# 12V_ESB.net
KiCad netlist of a schematic drawn in Altium Designer
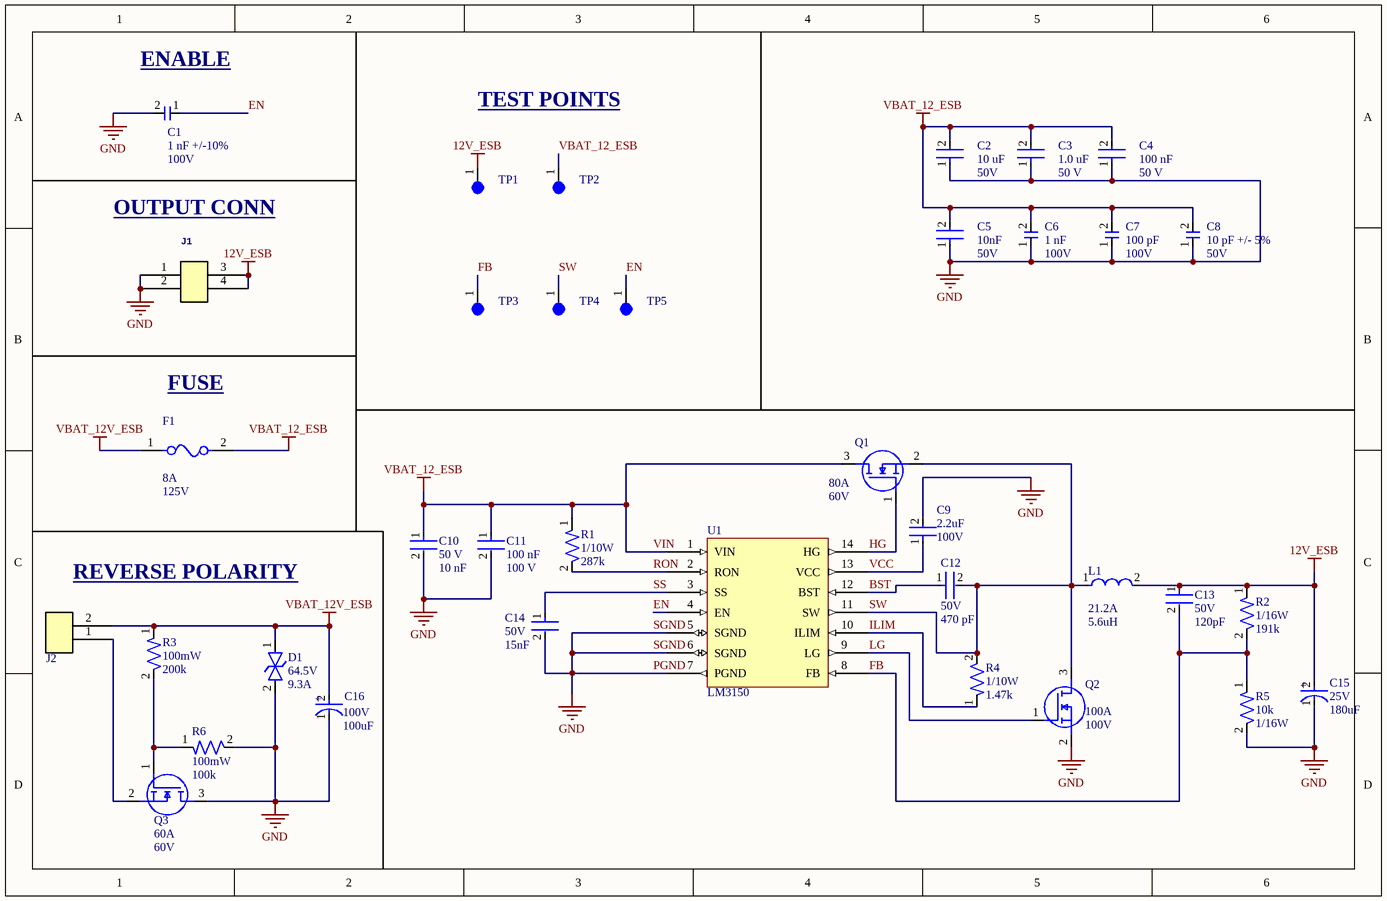
[diagram p0: 12V_ESB.SchDoc]

(export (version "E")
  (design (tool "Eeschema 10.0.6"))
  (components
    (comp (ref "C1")
      (value "C0603Y102K1RAC7867")
      (footprint "CAP-0603")
      (description "1000 pF ±10% 100V Ceramic Capacitor X7R 0603 (1608 Metric)")
      (fields (field (name "CAPACITANCE") "1 nF +/-10%") (field (name "VOLTAGE") "100V"))
      (libsource (lib "MasterLib") (part "CAP-1N-0001"))
    )
    (comp (ref "C2")
      (value "CL32B106KBJNNNE")
      (footprint "JLC_25:CAP-1210")
      (description "CAP CER 10UF 50V X7R 1210")
      (fields (field (name "VOLTAGE") "50V") (field (name "CAPACITANCE") "10 uF"))
      (libsource (lib "JLC_25") (part "CAP-10U-0002"))
    )
    (comp (ref "C3")
      (value "CC0805KKX7R9BB105")
      (footprint "JLC_25:CAP-0805")
      (description "CAP CER 1UF 50V X7R 0805")
      (fields (field (name "VOLTAGE") "50 V") (field (name "CAPACITANCE") "1.0 uF"))
      (libsource (lib "JLC_25") (part "CAP-1U-0001"))
    )
    (comp (ref "C4")
      (value "CC0805KRX7R9BB104")
      (footprint "JLC_25:CAP-0805")
      (description "CAP CER 0.1UF 50V X7R 0805")
      (fields (field (name "VOLTAGE RATING") "50 V") (field (name "CAPACITANCE") "100 nF"))
      (libsource (lib "JLC_25") (part "CAP-0.1U-0002"))
    )
    (comp (ref "C5")
      (value "GRM2195C1H103JA01D")
      (footprint "JLC_25:CAP-0805")
      (description "CAP CER 10000PF 50V C0G/NP0 0805")
      (fields (field (name "VOLTAGE") "50V") (field (name "CAPACITANCE") "10nF"))
      (libsource (lib "JLC_25") (part "CAP-10N-0001"))
    )
    (comp (ref "C6")
      (value "CDR01BX102BKUS7185")
      (footprint "CAP-0805")
      (description "1000 pF ±10% 100V Ceramic Capacitor BX 0805 (2012 Metric)")
      (fields (field (name "CAPACITANCE") "1 nF") (field (name "VOLTAGE RATING") "100V"))
      (libsource (lib "MasterLib") (part "CAP-1N-0003"))
    )
    (comp (ref "C7")
      (value "0603N101J101CT")
      (footprint "CAP-0603")
      (description "100 pF ±5% 100V Ceramic Capacitor C0G, NP0 0603 (1608 Metric)")
      (fields
        (field (name "TOLERANCE") "+/-5%")
        (field (name "CAPACITANCE") "100 pF")
        (field (name "VOLTAGE") "100V")
      )
      (libsource (lib "MasterLib") (part "CAP-100P-0002"))
    )
    (comp (ref "C8")
      (value "0603N100J500CT")
      (footprint "CAP-0603")
      (description "10 pF ±5% 50V Ceramic Capacitor C0G, NP0 0603 (1608 Metric)")
      (fields
        (field (name "MANUFACTURER") "Walshin Technology Corporation")
        (field (name "CAPACITANCE") "10 pF +/- 5%")
        (field (name "VOLTAGE RATING") "50V")
      )
      (libsource (lib "MasterLib") (part "CAP-10P-0001"))
    )
    (comp (ref "C9")
      (value "CC1206KKX7R0BB225")
      (footprint "CAP-1206")
      (description "CAP CER 2.2UF 100V X7R 1206")
      (fields (field (name "CAPACITANCE") "2.2uF") (field (name "VOLTAGE") "100V"))
      (libsource (lib "JLC_25") (part "CAP-2.2U-0001"))
    )
    (comp (ref "C10")
      (value "CC0603KPX7R9BB103")
      (footprint "CAP-0603")
      (description "CAP CER 10000PF 50V X7R 0603")
      (fields (field (name "VOLTAGE") "50 V") (field (name "CAPACITANCE") "10 nF"))
      (libsource (lib "JLC_25") (part "CAP-10N-0002"))
    )
    (comp (ref "C11")
      (value "CC0603KRX7R0BB104")
      (footprint "CAP-0603")
      (description "CAP CER 0.1UF 100V X7R 0603")
      (fields (field (name "CAPACITANCE") "100 nF") (field (name "VOLTAGE") "100 V"))
      (libsource (lib "JLC_25") (part "CAP-100N-0001"))
    )
    (comp (ref "C12")
      (value "CC0805JRNPO9BN471")
      (footprint "CAP-0805")
      (description "CAP CER 470PF 50V C0G/NPO 0805")
      (fields (field (name "VOLTAGE") "50V") (field (name "CAPACITANCE") "470 pF"))
      (libsource (lib "JLC_25") (part "CAP-470P-0001"))
    )
    (comp (ref "C13")
      (value "CC0603JRNPO9BN121")
      (footprint "CAP-0603")
      (description "CAP CER 120PF 50V C0G/NPO 0603")
      (fields (field (name "VOLTAGE") "50V") (field (name "CAPACITANCE") "120pF"))
      (libsource (lib "JLC_25") (part "CAP-120pF-0001"))
    )
    (comp (ref "C14")
      (value "CC0402KRX7R9BB153")
      (footprint "CAP-0402")
      (description "50V 15nF X7R ±10% 0402 Multilayer Ceramic Capacitors MLCC - SMD/SMT ROHS")
      (fields (field (name "VOLTAGE") "50V") (field (name "CAPACITANCE") "15nF"))
      (libsource (lib "JLC_25") (part "CAP-15N-0001"))
    )
    (comp (ref "C15")
      (value "EEE-FNE181XUP")
      (footprint "CAP-180uF")
      (description "CAP ALUM 180UF 20% 25V SMD")
      (fields (field (name "VOLTAGE") "25V") (field (name "CAPACITANCE") "180uF"))
      (libsource (lib "JLC_25") (part "CAP-180uF-0001"))
    )
    (comp (ref "C16")
      (value "100SEV100M12.5X16")
      (footprint "CAP-100U-0002")
      (description "100 µF 100 V Aluminum Electrolytic Capacitors Radial, Can - SMD 2000 Hrs @ 85°C")
      (fields (field (name "VOLTAGE") "100V") (field (name "CAPACITANCE") "100uF"))
      (libsource (lib "JLC_25") (part "CAP-100U-0002"))
    )
    (comp (ref "D1")
      (value "SMBJ40CA")
      (footprint "DO-214AA (SMBJ)")
      (description "TVS DIODE 40VWM 64.5VC DO214AA")
      (fields (field (name "VOLTAGE RATING") "64.5V") (field (name "CURRENT RATING") "9.3A"))
      (libsource (lib "JLC_25") (part "DIO-TVS-0001"))
    )
    (comp (ref "F1")
      (value "01550900M")
      (footprint "FUSE-0001")
      (description "FUSE BLOK CARTRIDGE 125V 10A SMD")
      (fields (field (name "FUSE CURRENT") "8A") (field (name "VOLTAGE RATING") "125V"))
      (libsource (lib "JLC_25") (part "FUSE-0001"))
    )
    (comp (ref "J1")
      (value "Molex 43045-0412")
      (footprint "CONN-4POS-0002")
      (description "CONN HEADER VERT 4POS 3MM")
      (libsource (lib "JLC_25") (part "CONN-4POS-0002"))
    )
    (comp (ref "J2")
      (value "1546927-2")
      (footprint "CONN-1546927-2")
      (libsource (lib "JLC_25") (part "CONN-2POS-0003"))
    )
    (comp (ref "L1")
      (value "FEXL1010A-5R6M")
      (footprint "IND-5.6UH-0002")
      (description "21.2A 5.6uH Integrated molded inductor ±20% 23.6A SMD,11x11.9mm Power Inductors ROHS")
      (fields (field (name "CURRENT RATING") "21.2A") (field (name "INDUCTANCE") "5.6uH"))
      (libsource (lib "JLC_25") (part "IND-5.6U-0002"))
    )
    (comp (ref "Q1")
      (value "RU6080L")
      (footprint "NMOS-80A-0001")
      (description "60V 80A 7mΩ@10V,30A 125W 3V TO-252-2 MOSFETs ROHS")
      (fields (field (name "CONTINUOUS CURRENT") "80A") (field (name "VOLTAGE") "60V"))
      (libsource (lib "JLC_25") (part "NMOS-80A-0001"))
    )
    (comp (ref "Q2")
      (value "CSD19533Q5A")
      (footprint "NMOS-100A")
      (description "100V 100A 7.8mΩ@10V,13A 3.2W 2.8V 1 N-channel VSONP-8(5x6) MOSFETs ROHS")
      (fields (field (name "CONTINUOUS CURRENT") "100A") (field (name "VOLTAGE") "100V"))
      (libsource (lib "JLC_25") (part "NMOS-100A-0001"))
    )
    (comp (ref "Q3")
      (value "CSD18543Q3AT")
      (footprint "IC-8VSONCLIP")
      (description "MOSFET N-CH 60V 12A/60A 8VSON")
      (fields (field (name "VOLTAGE") "60V") (field (name "CONTINUOUS CURRENT") "60A"))
      (libsource (lib "JLC_25") (part "NMOS-60A-0001"))
    )
    (comp (ref "R1")
      (value "RC0603FR-07287KL")
      (footprint "RES-0603")
      (description "RES 287K OHM 1% 1/10W 0603")
      (fields (field (name "POWER") "1/10W") (field (name "RESISTANCE") "287k"))
      (libsource (lib "JLC_25") (part "RES-287k-0001"))
    )
    (comp (ref "R2")
      (value "RC0402FR-07191KL")
      (footprint "RES-0402")
      (description "191 kOhms ±1% 0.063W, 1/16W Chip Resistor 0402 (1005 Metric) Moisture Resistant Thick Film")
      (fields (field (name "POWER") "1/16W") (field (name "RESISTANCE") "191k"))
      (libsource (lib "JLC_25") (part "RES-191k-0001"))
    )
    (comp (ref "R3")
      (value "RC0603FR-07200KL")
      (footprint "RES-0603")
      (description "RES SMD 200K OHM 1% 1/10W 0603")
      (fields
        (field (name "TOLERANCE") "1%")
        (field (name "POWER") "100mW")
        (field (name "RESISTANCE") "200k")
      )
      (libsource (lib "JLC_25") (part "RES-200k-0001"))
    )
    (comp (ref "R4")
      (value "RC0603FR-071K47L")
      (footprint "RES-0603")
      (description "RES 1.47K OHM 1% 1/10W 0603")
      (fields (field (name "POWER") "1/10W") (field (name "RESISTANCE") "1.47k"))
      (libsource (lib "JLC_25") (part "RES-1.47k-0001"))
    )
    (comp (ref "R5")
      (value "RC0402FR-0710KL")
      (footprint "RES-0402")
      (description "RES 10K OHM 1% 1/16W 0402")
      (fields
        (field (name "TOLERANCE") "1%")
        (field (name "RESISTANCE") "10k")
        (field (name "POWER") "1/16W")
      )
      (libsource (lib "JLC_25") (part "RES-10k-0001"))
    )
    (comp (ref "R6")
      (value "RC0603FR-07100KL")
      (footprint "RES-0603")
      (description "RES SMD 100K OHM 1% 1/10W 0603")
      (fields
        (field (name "TOLERANCE") "1%")
        (field (name "POWER") "100mW")
        (field (name "RESISTANCE") "100k")
      )
      (libsource (lib "JLC_25") (part "RES-100k-0001"))
    )
    (comp (ref "TP1")
      (value "5003")
      (footprint "TEST-POINT-0001")
      (description "Oranange PC Test Point, Miniature Phoisphor Bronze Silver Plating Through Hole Mounting Type")
      (libsource (lib "*") (part "TEST-POINT-0001"))
    )
    (comp (ref "TP2")
      (value "5003")
      (footprint "TEST-POINT-0001")
      (description "Oranange PC Test Point, Miniature Phoisphor Bronze Silver Plating Through Hole Mounting Type")
      (libsource (lib "*") (part "TEST-POINT-0001"))
    )
    (comp (ref "TP3")
      (value "5003")
      (footprint "TEST-POINT-0001")
      (description "Oranange PC Test Point, Miniature Phoisphor Bronze Silver Plating Through Hole Mounting Type")
      (libsource (lib "*") (part "TEST-POINT-0001"))
    )
    (comp (ref "TP4")
      (value "5003")
      (footprint "TEST-POINT-0001")
      (description "Oranange PC Test Point, Miniature Phoisphor Bronze Silver Plating Through Hole Mounting Type")
      (libsource (lib "*") (part "TEST-POINT-0001"))
    )
    (comp (ref "TP5")
      (value "5003")
      (footprint "TEST-POINT-0001")
      (description "Oranange PC Test Point, Miniature Phoisphor Bronze Silver Plating Through Hole Mounting Type")
      (libsource (lib "*") (part "TEST-POINT-0001"))
    )
    (comp (ref "U1")
      (value "LM3150")
      (footprint "IC_ESB")
      (description "Buck Regulator Positive Output Step-Down DC-DC Controller IC 14-HTSSOP")
      (libsource (lib "MasterLib") (part "IC-ESB-0001"))
    )
  )
  (nets
    (net (code "1") (name "/BST") (class "Default")
      (node (ref "C12") (pin "1") (pinfunction "1_1") (pintype "passive"))
      (node (ref "U1") (pin "12") (pinfunction "BST_12") (pintype "input"))
    )
    (net (code "2") (name "/EN") (class "Default")
      (node (ref "C1") (pin "1") (pinfunction "1_1") (pintype "passive"))
      (node (ref "TP5") (pin "1") (pinfunction "0_1") (pintype "passive"))
      (node (ref "U1") (pin "4") (pinfunction "EN_4") (pintype "input"))
    )
    (net (code "3") (name "/FB") (class "Default")
      (node (ref "C13") (pin "2") (pinfunction "2_2") (pintype "passive"))
      (node (ref "R2") (pin "2") (pinfunction "2_2") (pintype "passive"))
      (node (ref "R5") (pin "1") (pinfunction "1_1") (pintype "passive"))
      (node (ref "TP3") (pin "1") (pinfunction "0_1") (pintype "passive"))
      (node (ref "U1") (pin "8") (pinfunction "FB_8") (pintype "input"))
    )
    (net (code "4") (name "/HG") (class "Default")
      (node (ref "Q1") (pin "1") (pinfunction "G_1") (pintype "passive"))
      (node (ref "U1") (pin "14") (pinfunction "HG_14") (pintype "output"))
    )
    (net (code "5") (name "/ILIM") (class "Default")
      (node (ref "R4") (pin "1") (pinfunction "1_1") (pintype "passive"))
      (node (ref "U1") (pin "10") (pinfunction "ILIM_10") (pintype "input"))
    )
    (net (code "6") (name "/LG") (class "Default")
      (node (ref "Q2") (pin "1") (pinfunction "G_1") (pintype "passive"))
      (node (ref "U1") (pin "9") (pinfunction "LG_9") (pintype "output"))
    )
    (net (code "7") (name "/RON") (class "Default")
      (node (ref "R1") (pin "2") (pinfunction "2_2") (pintype "passive"))
      (node (ref "U1") (pin "2") (pinfunction "RON_2") (pintype "input"))
    )
    (net (code "8") (name "/SS") (class "Default")
      (node (ref "C14") (pin "1") (pinfunction "1_1") (pintype "passive"))
      (node (ref "U1") (pin "3") (pinfunction "SS_3") (pintype "input"))
    )
    (net (code "9") (name "/SW") (class "Default")
      (node (ref "C12") (pin "2") (pinfunction "2_2") (pintype "passive"))
      (node (ref "L1") (pin "1") (pinfunction "1_1") (pintype "passive"))
      (node (ref "Q1") (pin "2") (pinfunction "S_2") (pintype "passive"))
      (node (ref "Q2") (pin "3") (pinfunction "D_3") (pintype "passive"))
      (node (ref "R4") (pin "2") (pinfunction "2_2") (pintype "passive"))
      (node (ref "TP4") (pin "1") (pinfunction "0_1") (pintype "passive"))
      (node (ref "U1") (pin "11") (pinfunction "SW_11") (pintype "output"))
    )
    (net (code "10") (name "/VCC") (class "Default")
      (node (ref "C9") (pin "1") (pinfunction "1_1") (pintype "passive"))
      (node (ref "U1") (pin "13") (pinfunction "VCC_13") (pintype "output"))
    )
    (net (code "11") (name "12V_ESB") (class "Default")
      (node (ref "C13") (pin "1") (pinfunction "1_1") (pintype "passive"))
      (node (ref "C15") (pin "2") (pinfunction "1_2") (pintype "passive"))
      (node (ref "J1") (pin "3") (pinfunction "3_3") (pintype "passive"))
      (node (ref "J1") (pin "4") (pinfunction "4_4") (pintype "passive"))
      (node (ref "L1") (pin "2") (pinfunction "2_2") (pintype "passive"))
      (node (ref "R2") (pin "1") (pinfunction "1_1") (pintype "passive"))
      (node (ref "TP1") (pin "1") (pinfunction "0_1") (pintype "passive"))
    )
    (net (code "12") (name "GND") (class "Default")
      (node (ref "C1") (pin "2") (pinfunction "2_2") (pintype "passive"))
      (node (ref "C10") (pin "2") (pinfunction "2_2") (pintype "passive"))
      (node (ref "C11") (pin "2") (pinfunction "2_2") (pintype "passive"))
      (node (ref "C14") (pin "2") (pinfunction "2_2") (pintype "passive"))
      (node (ref "C15") (pin "1") (pinfunction "2_1") (pintype "passive"))
      (node (ref "C16") (pin "1") (pinfunction "2_1") (pintype "passive"))
      (node (ref "C2") (pin "1") (pinfunction "1_1") (pintype "passive"))
      (node (ref "C3") (pin "1") (pinfunction "1_1") (pintype "passive"))
      (node (ref "C4") (pin "1") (pinfunction "1_1") (pintype "passive"))
      (node (ref "C5") (pin "1") (pinfunction "1_1") (pintype "passive"))
      (node (ref "C6") (pin "1") (pinfunction "1_1") (pintype "passive"))
      (node (ref "C7") (pin "1") (pinfunction "1_1") (pintype "passive"))
      (node (ref "C8") (pin "1") (pinfunction "1_1") (pintype "passive"))
      (node (ref "C9") (pin "2") (pinfunction "2_2") (pintype "passive"))
      (node (ref "D1") (pin "2") (pintype "passive"))
      (node (ref "J1") (pin "1") (pinfunction "1_1") (pintype "passive"))
      (node (ref "J1") (pin "2") (pinfunction "2_2") (pintype "passive"))
      (node (ref "Q2") (pin "2") (pinfunction "S_2") (pintype "passive"))
      (node (ref "Q3") (pin "3") (pinfunction "D_3") (pintype "passive"))
      (node (ref "R5") (pin "2") (pinfunction "2_2") (pintype "passive"))
      (node (ref "R6") (pin "2") (pinfunction "2_2") (pintype "passive"))
      (node (ref "U1") (pin "5") (pinfunction "SGND_5") (pintype "bidirectional"))
      (node (ref "U1") (pin "6") (pinfunction "SGND_6") (pintype "bidirectional"))
      (node (ref "U1") (pin "7") (pinfunction "PGND_7") (pintype "output"))
    )
    (net (code "13") (name "Net-(J2-7)") (class "Default")
      (node (ref "J2") (pin "1") (pinfunction "7_1") (pintype "passive"))
      (node (ref "Q3") (pin "2") (pinfunction "S_2") (pintype "passive"))
    )
    (net (code "14") (name "Net-(Q3-G)") (class "Default")
      (node (ref "Q3") (pin "1") (pinfunction "G_1") (pintype "passive"))
      (node (ref "R3") (pin "2") (pinfunction "2_2") (pintype "passive"))
      (node (ref "R6") (pin "1") (pinfunction "1_1") (pintype "passive"))
    )
    (net (code "15") (name "VBAT_12V_ESB") (class "Default")
      (node (ref "C16") (pin "2") (pinfunction "1_2") (pintype "passive"))
      (node (ref "D1") (pin "1") (pintype "passive"))
      (node (ref "F1") (pin "1") (pinfunction "1_1") (pintype "passive"))
      (node (ref "J2") (pin "2") (pinfunction "8_2") (pintype "passive"))
      (node (ref "R3") (pin "1") (pinfunction "1_1") (pintype "passive"))
    )
    (net (code "16") (name "VBAT_12_ESB") (class "Default")
      (node (ref "C10") (pin "1") (pinfunction "1_1") (pintype "passive"))
      (node (ref "C11") (pin "1") (pinfunction "1_1") (pintype "passive"))
      (node (ref "C2") (pin "2") (pinfunction "2_2") (pintype "passive"))
      (node (ref "C3") (pin "2") (pinfunction "2_2") (pintype "passive"))
      (node (ref "C4") (pin "2") (pinfunction "2_2") (pintype "passive"))
      (node (ref "C5") (pin "2") (pinfunction "2_2") (pintype "passive"))
      (node (ref "C6") (pin "2") (pinfunction "2_2") (pintype "passive"))
      (node (ref "C7") (pin "2") (pinfunction "2_2") (pintype "passive"))
      (node (ref "C8") (pin "2") (pinfunction "2_2") (pintype "passive"))
      (node (ref "F1") (pin "2") (pinfunction "2_2") (pintype "passive"))
      (node (ref "Q1") (pin "3") (pinfunction "D_3") (pintype "passive"))
      (node (ref "R1") (pin "1") (pinfunction "1_1") (pintype "passive"))
      (node (ref "TP2") (pin "1") (pinfunction "0_1") (pintype "passive"))
      (node (ref "U1") (pin "1") (pinfunction "VIN_1") (pintype "input"))
    )
  )
)
